# H723.net
KiCad netlist of a schematic drawn in EasyEDA Pro
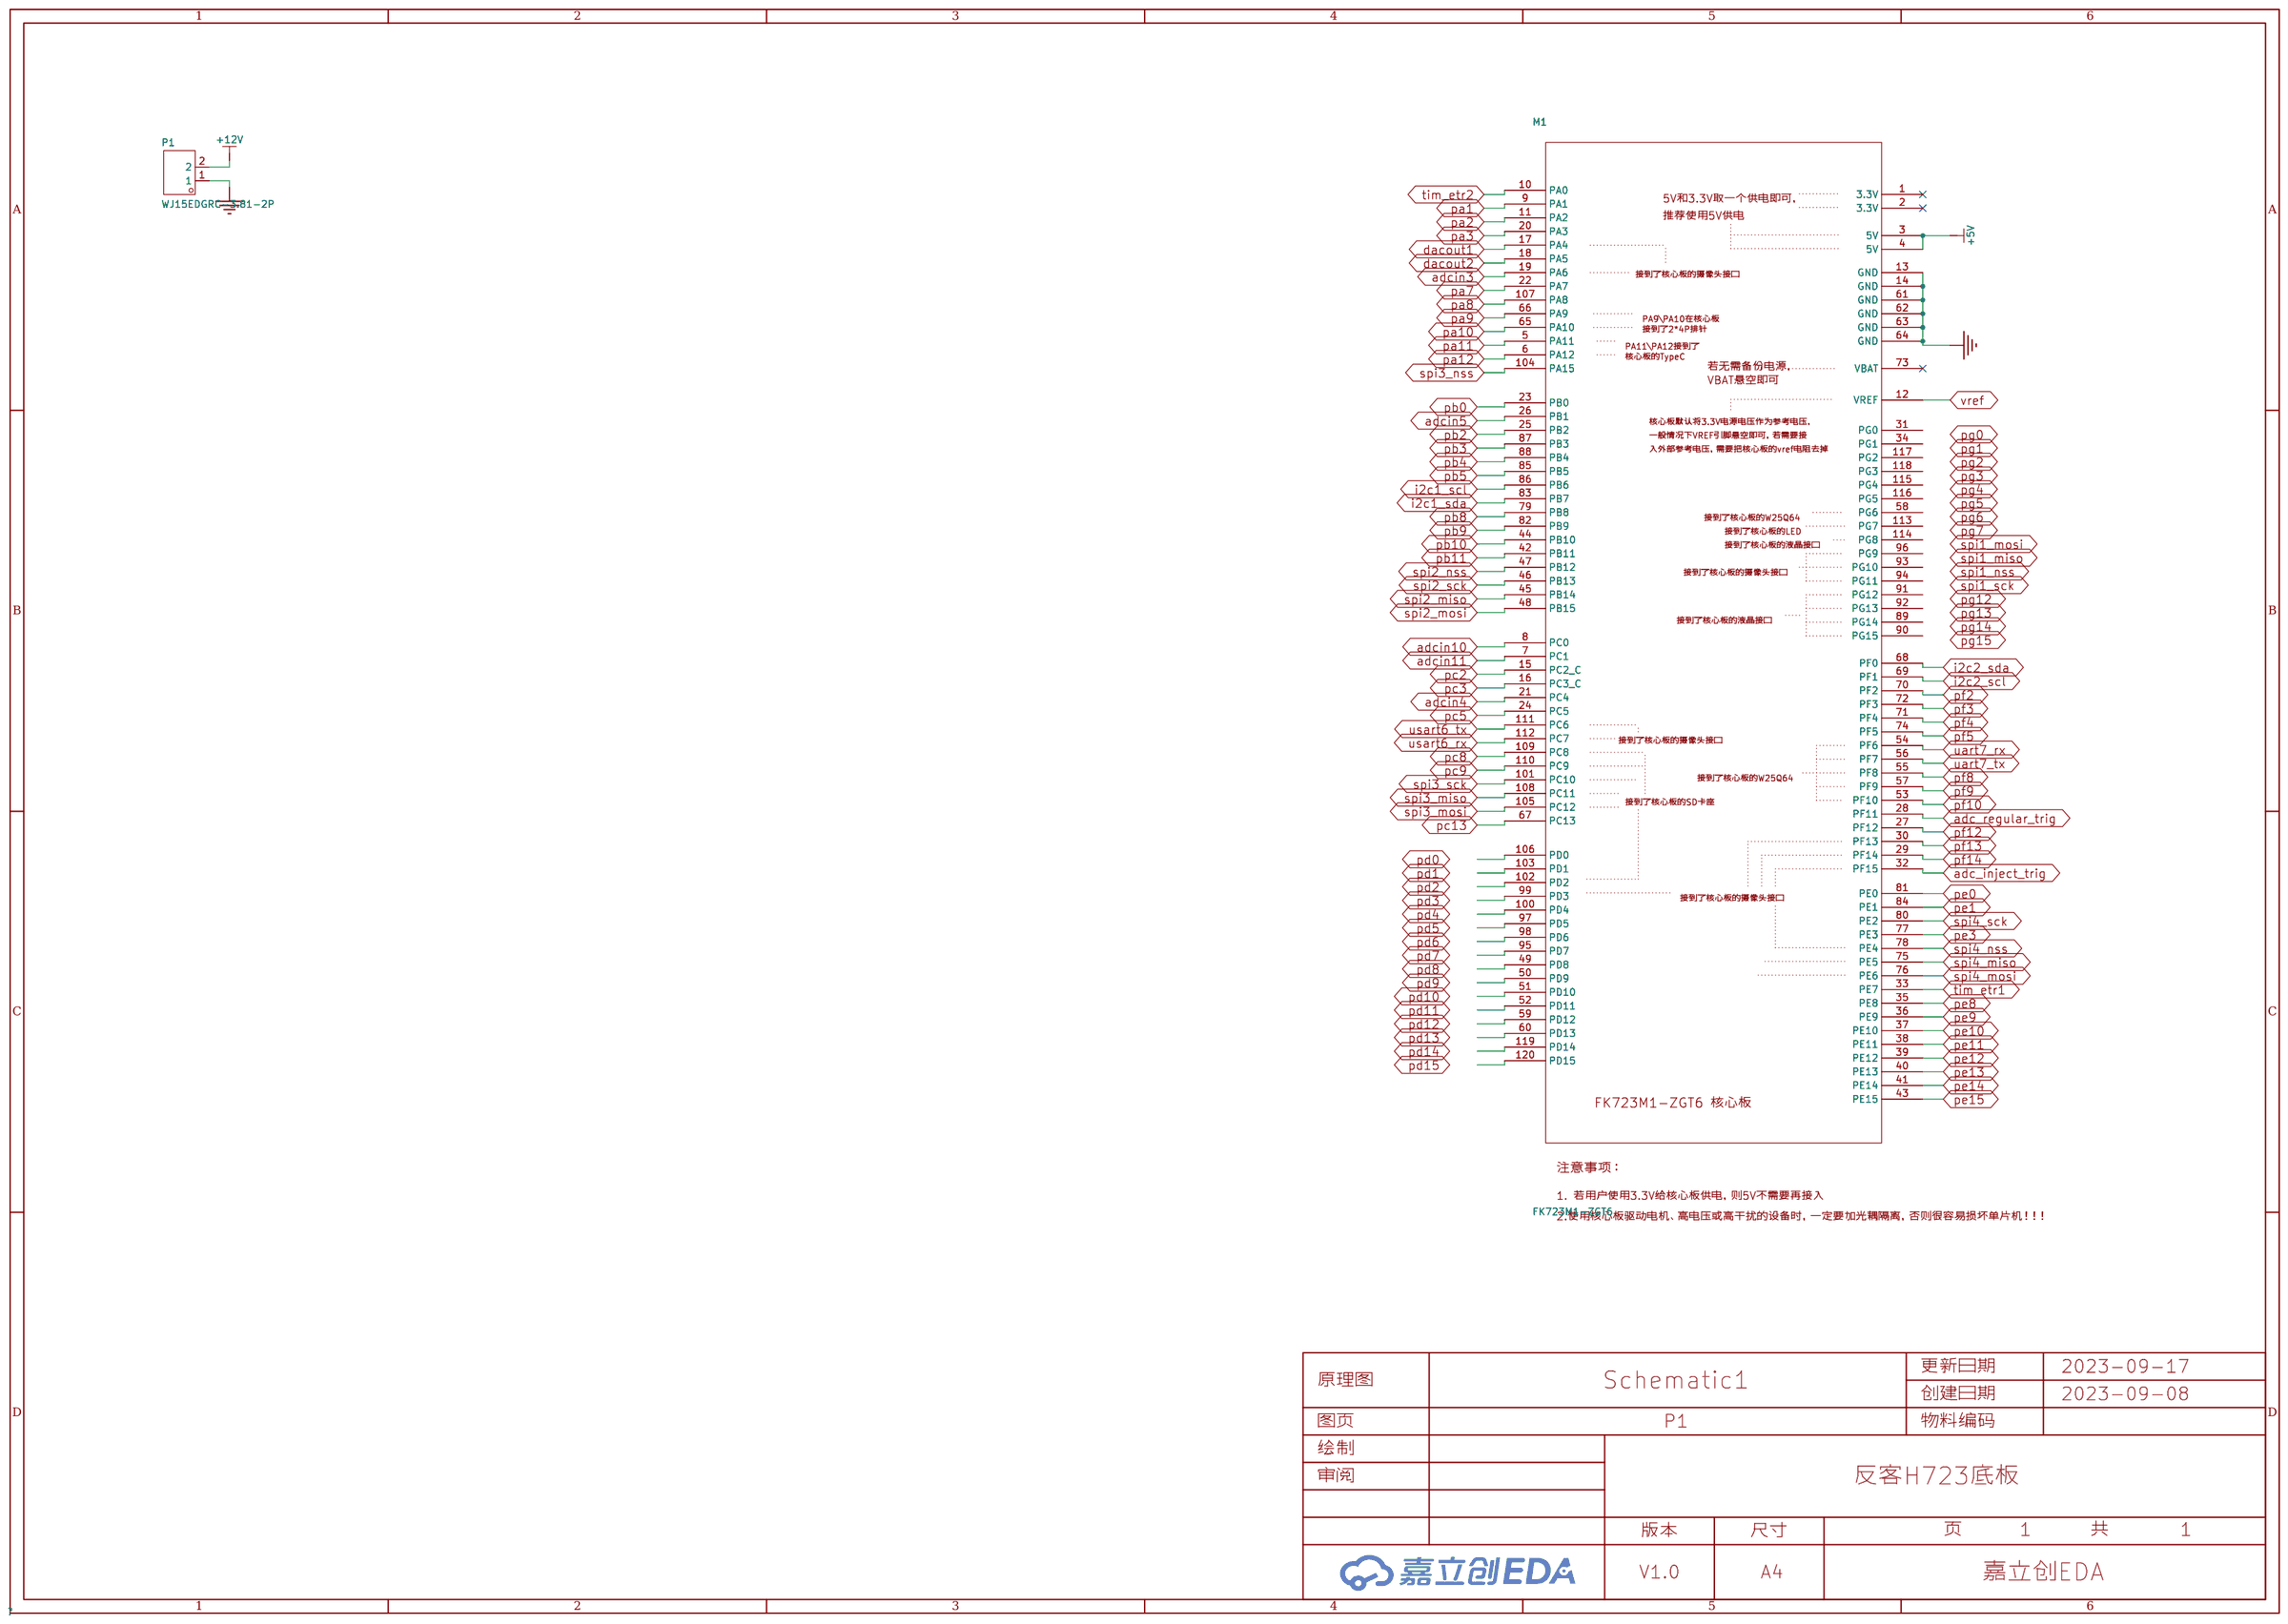
[diagram p0: schematic sheet]

(export (version "E")
  (design (tool "Eeschema 10.0.6"))
  (components
    (comp (ref "M1")
      (value "FK723M1-ZGT6")
      (footprint "easyedapro:FK723M1-ZGT6")
      (libsource (lib "easyedapro") (part "FK723M1-ZGT6"))
    )
    (comp (ref "P1")
      (value "WJ15EDGRC-3.81-2P")
      (footprint "easyedapro:CONN-TH_2P-P3.81_WJ15EDGRC-3.81-2P")
      (description "连接器类型:板端/插座-闭口;间距:3.81mm;排数:1;每排PIN数:2;安装方式:弯针;颜色:绿色;")
      (fields (field (name "Manufacturer") "KANGNEX(康奈克斯电气)"))
      (libsource (lib "easyedapro") (part "WJ15EDGRC-3.81-2P"))
    )
  )
  (nets
    (net (code "1") (name "+5V") (class "Default")
      (node (ref "M1") (pin "3") (pinfunction "5V_3") (pintype "input"))
      (node (ref "M1") (pin "4") (pinfunction "5V_4") (pintype "input"))
    )
    (net (code "2") (name "+12V") (class "Default")
      (node (ref "P1") (pin "2") (pinfunction "2_2") (pintype "input"))
    )
    (net (code "3") (name "GND") (class "Default")
      (node (ref "M1") (pin "13") (pinfunction "GND_13") (pintype "input"))
      (node (ref "M1") (pin "14") (pinfunction "GND_14") (pintype "input"))
      (node (ref "M1") (pin "61") (pinfunction "GND_61") (pintype "input"))
      (node (ref "M1") (pin "62") (pinfunction "GND_62") (pintype "input"))
      (node (ref "M1") (pin "63") (pinfunction "GND_63") (pintype "input"))
      (node (ref "M1") (pin "64") (pinfunction "GND_64") (pintype "input"))
      (node (ref "P1") (pin "1") (pinfunction "1_1") (pintype "input"))
    )
    (net (code "4") (name "adc_inject_trig") (class "Default")
      (node (ref "M1") (pin "32") (pinfunction "PF15_32") (pintype "input"))
    )
    (net (code "5") (name "adc_regular_trig") (class "Default")
      (node (ref "M1") (pin "28") (pinfunction "PF11_28") (pintype "input"))
    )
    (net (code "6") (name "adcin3") (class "Default")
      (node (ref "M1") (pin "19") (pinfunction "PA6_19") (pintype "input"))
    )
    (net (code "7") (name "adcin4") (class "Default")
      (node (ref "M1") (pin "21") (pinfunction "PC4_21") (pintype "input"))
    )
    (net (code "8") (name "adcin5") (class "Default")
      (node (ref "M1") (pin "26") (pinfunction "PB1_26") (pintype "input"))
    )
    (net (code "9") (name "adcin10") (class "Default")
      (node (ref "M1") (pin "8") (pinfunction "PC0_8") (pintype "input"))
    )
    (net (code "10") (name "adcin11") (class "Default")
      (node (ref "M1") (pin "7") (pinfunction "PC1_7") (pintype "input"))
    )
    (net (code "11") (name "dacout1") (class "Default")
      (node (ref "M1") (pin "17") (pinfunction "PA4_17") (pintype "input"))
    )
    (net (code "12") (name "dacout2") (class "Default")
      (node (ref "M1") (pin "18") (pinfunction "PA5_18") (pintype "input"))
    )
    (net (code "13") (name "i2c1_scl") (class "Default")
      (node (ref "M1") (pin "86") (pinfunction "PB6_86") (pintype "input"))
    )
    (net (code "14") (name "i2c1_sda") (class "Default")
      (node (ref "M1") (pin "83") (pinfunction "PB7_83") (pintype "input"))
    )
    (net (code "15") (name "i2c2_scl") (class "Default")
      (node (ref "M1") (pin "69") (pinfunction "PF1_69") (pintype "input"))
    )
    (net (code "16") (name "i2c2_sda") (class "Default")
      (node (ref "M1") (pin "68") (pinfunction "PF0_68") (pintype "input"))
    )
    (net (code "17") (name "pa1") (class "Default")
      (node (ref "M1") (pin "9") (pinfunction "PA1_9") (pintype "input"))
    )
    (net (code "18") (name "pa2") (class "Default")
      (node (ref "M1") (pin "11") (pinfunction "PA2_11") (pintype "input"))
    )
    (net (code "19") (name "pa3") (class "Default")
      (node (ref "M1") (pin "20") (pinfunction "PA3_20") (pintype "input"))
    )
    (net (code "20") (name "pa7") (class "Default")
      (node (ref "M1") (pin "22") (pinfunction "PA7_22") (pintype "input"))
    )
    (net (code "21") (name "pa8") (class "Default")
      (node (ref "M1") (pin "107") (pinfunction "PA8_107") (pintype "input"))
    )
    (net (code "22") (name "pa9") (class "Default")
      (node (ref "M1") (pin "66") (pinfunction "PA9_66") (pintype "input"))
    )
    (net (code "23") (name "pa10") (class "Default")
      (node (ref "M1") (pin "65") (pinfunction "PA10_65") (pintype "input"))
    )
    (net (code "24") (name "pa11") (class "Default")
      (node (ref "M1") (pin "5") (pinfunction "PA11_5") (pintype "input"))
    )
    (net (code "25") (name "pa12") (class "Default")
      (node (ref "M1") (pin "6") (pinfunction "PA12_6") (pintype "input"))
    )
    (net (code "26") (name "pb0") (class "Default")
      (node (ref "M1") (pin "23") (pinfunction "PB0_23") (pintype "input"))
    )
    (net (code "27") (name "pb2") (class "Default")
      (node (ref "M1") (pin "25") (pinfunction "PB2_25") (pintype "input"))
    )
    (net (code "28") (name "pb3") (class "Default")
      (node (ref "M1") (pin "87") (pinfunction "PB3_87") (pintype "input"))
    )
    (net (code "29") (name "pb4") (class "Default")
      (node (ref "M1") (pin "88") (pinfunction "PB4_88") (pintype "input"))
    )
    (net (code "30") (name "pb5") (class "Default")
      (node (ref "M1") (pin "85") (pinfunction "PB5_85") (pintype "input"))
    )
    (net (code "31") (name "pb8") (class "Default")
      (node (ref "M1") (pin "79") (pinfunction "PB8_79") (pintype "input"))
    )
    (net (code "32") (name "pb9") (class "Default")
      (node (ref "M1") (pin "82") (pinfunction "PB9_82") (pintype "input"))
    )
    (net (code "33") (name "pb10") (class "Default")
      (node (ref "M1") (pin "44") (pinfunction "PB10_44") (pintype "input"))
    )
    (net (code "34") (name "pb11") (class "Default")
      (node (ref "M1") (pin "42") (pinfunction "PB11_42") (pintype "input"))
    )
    (net (code "35") (name "pc2") (class "Default")
      (node (ref "M1") (pin "15") (pinfunction "PC2_C_15") (pintype "input"))
    )
    (net (code "36") (name "pc3") (class "Default")
      (node (ref "M1") (pin "16") (pinfunction "PC3_C_16") (pintype "input"))
    )
    (net (code "37") (name "pc5") (class "Default")
      (node (ref "M1") (pin "24") (pinfunction "PC5_24") (pintype "input"))
    )
    (net (code "38") (name "pc8") (class "Default")
      (node (ref "M1") (pin "109") (pinfunction "PC8_109") (pintype "input"))
    )
    (net (code "39") (name "pc9") (class "Default")
      (node (ref "M1") (pin "110") (pinfunction "PC9_110") (pintype "input"))
    )
    (net (code "40") (name "pc13") (class "Default")
      (node (ref "M1") (pin "67") (pinfunction "PC13_67") (pintype "input"))
    )
    (net (code "57") (name "pe0") (class "Default")
      (node (ref "M1") (pin "81") (pinfunction "PE0_81") (pintype "input"))
    )
    (net (code "58") (name "pe1") (class "Default")
      (node (ref "M1") (pin "84") (pinfunction "PE1_84") (pintype "input"))
    )
    (net (code "59") (name "pe3") (class "Default")
      (node (ref "M1") (pin "77") (pinfunction "PE3_77") (pintype "input"))
    )
    (net (code "60") (name "pe8") (class "Default")
      (node (ref "M1") (pin "35") (pinfunction "PE8_35") (pintype "input"))
    )
    (net (code "61") (name "pe9") (class "Default")
      (node (ref "M1") (pin "36") (pinfunction "PE9_36") (pintype "input"))
    )
    (net (code "62") (name "pe10") (class "Default")
      (node (ref "M1") (pin "37") (pinfunction "PE10_37") (pintype "input"))
    )
    (net (code "63") (name "pe11") (class "Default")
      (node (ref "M1") (pin "38") (pinfunction "PE11_38") (pintype "input"))
    )
    (net (code "64") (name "pe12") (class "Default")
      (node (ref "M1") (pin "39") (pinfunction "PE12_39") (pintype "input"))
    )
    (net (code "65") (name "pe13") (class "Default")
      (node (ref "M1") (pin "40") (pinfunction "PE13_40") (pintype "input"))
    )
    (net (code "66") (name "pe14") (class "Default")
      (node (ref "M1") (pin "41") (pinfunction "PE14_41") (pintype "input"))
    )
    (net (code "67") (name "pe15") (class "Default")
      (node (ref "M1") (pin "43") (pinfunction "PE15_43") (pintype "input"))
    )
    (net (code "68") (name "pf2") (class "Default")
      (node (ref "M1") (pin "70") (pinfunction "PF2_70") (pintype "input"))
    )
    (net (code "69") (name "pf3") (class "Default")
      (node (ref "M1") (pin "72") (pinfunction "PF3_72") (pintype "input"))
    )
    (net (code "70") (name "pf4") (class "Default")
      (node (ref "M1") (pin "71") (pinfunction "PF4_71") (pintype "input"))
    )
    (net (code "71") (name "pf5") (class "Default")
      (node (ref "M1") (pin "74") (pinfunction "PF5_74") (pintype "input"))
    )
    (net (code "72") (name "pf8") (class "Default")
      (node (ref "M1") (pin "55") (pinfunction "PF8_55") (pintype "input"))
    )
    (net (code "73") (name "pf9") (class "Default")
      (node (ref "M1") (pin "57") (pinfunction "PF9_57") (pintype "input"))
    )
    (net (code "74") (name "pf10") (class "Default")
      (node (ref "M1") (pin "53") (pinfunction "PF10_53") (pintype "input"))
    )
    (net (code "75") (name "pf12") (class "Default")
      (node (ref "M1") (pin "27") (pinfunction "PF12_27") (pintype "input"))
    )
    (net (code "76") (name "pf13") (class "Default")
      (node (ref "M1") (pin "30") (pinfunction "PF13_30") (pintype "input"))
    )
    (net (code "77") (name "pf14") (class "Default")
      (node (ref "M1") (pin "29") (pinfunction "PF14_29") (pintype "input"))
    )
    (net (code "94") (name "spi2_miso") (class "Default")
      (node (ref "M1") (pin "45") (pinfunction "PB14_45") (pintype "input"))
    )
    (net (code "95") (name "spi2_mosi") (class "Default")
      (node (ref "M1") (pin "48") (pinfunction "PB15_48") (pintype "input"))
    )
    (net (code "96") (name "spi2_nss") (class "Default")
      (node (ref "M1") (pin "47") (pinfunction "PB12_47") (pintype "input"))
    )
    (net (code "97") (name "spi2_sck") (class "Default")
      (node (ref "M1") (pin "46") (pinfunction "PB13_46") (pintype "input"))
    )
    (net (code "98") (name "spi3_miso") (class "Default")
      (node (ref "M1") (pin "108") (pinfunction "PC11_108") (pintype "input"))
    )
    (net (code "99") (name "spi3_mosi") (class "Default")
      (node (ref "M1") (pin "105") (pinfunction "PC12_105") (pintype "input"))
    )
    (net (code "100") (name "spi3_nss") (class "Default")
      (node (ref "M1") (pin "104") (pinfunction "PA15_104") (pintype "input"))
    )
    (net (code "101") (name "spi3_sck") (class "Default")
      (node (ref "M1") (pin "101") (pinfunction "PC10_101") (pintype "input"))
    )
    (net (code "102") (name "spi4_miso") (class "Default")
      (node (ref "M1") (pin "75") (pinfunction "PE5_75") (pintype "input"))
    )
    (net (code "103") (name "spi4_mosi") (class "Default")
      (node (ref "M1") (pin "76") (pinfunction "PE6_76") (pintype "input"))
    )
    (net (code "104") (name "spi4_nss") (class "Default")
      (node (ref "M1") (pin "78") (pinfunction "PE4_78") (pintype "input"))
    )
    (net (code "105") (name "spi4_sck") (class "Default")
      (node (ref "M1") (pin "80") (pinfunction "PE2_80") (pintype "input"))
    )
    (net (code "106") (name "tim_etr1") (class "Default")
      (node (ref "M1") (pin "33") (pinfunction "PE7_33") (pintype "input"))
    )
    (net (code "107") (name "tim_etr2") (class "Default")
      (node (ref "M1") (pin "10") (pinfunction "PA0_10") (pintype "input"))
    )
    (net (code "108") (name "uart7_rx") (class "Default")
      (node (ref "M1") (pin "54") (pinfunction "PF6_54") (pintype "input"))
    )
    (net (code "109") (name "uart7_tx") (class "Default")
      (node (ref "M1") (pin "56") (pinfunction "PF7_56") (pintype "input"))
    )
    (net (code "110") (name "unconnected-(M1-3.3V-Pad1)") (class "Default")
      (node (ref "M1") (pin "1") (pinfunction "3.3V_1") (pintype "input+no_connect"))
    )
    (net (code "111") (name "unconnected-(M1-3.3V-Pad2)") (class "Default")
      (node (ref "M1") (pin "2") (pinfunction "3.3V_2") (pintype "input+no_connect"))
    )
    (net (code "112") (name "unconnected-(M1-PD0-Pad106)") (class "Default")
      (node (ref "M1") (pin "106") (pinfunction "PD0_106") (pintype "input"))
    )
    (net (code "113") (name "unconnected-(M1-PD1-Pad103)") (class "Default")
      (node (ref "M1") (pin "103") (pinfunction "PD1_103") (pintype "input"))
    )
    (net (code "114") (name "unconnected-(M1-PD2-Pad102)") (class "Default")
      (node (ref "M1") (pin "102") (pinfunction "PD2_102") (pintype "input"))
    )
    (net (code "115") (name "unconnected-(M1-PD3-Pad99)") (class "Default")
      (node (ref "M1") (pin "99") (pinfunction "PD3_99") (pintype "input"))
    )
    (net (code "116") (name "unconnected-(M1-PD4-Pad100)") (class "Default")
      (node (ref "M1") (pin "100") (pinfunction "PD4_100") (pintype "input"))
    )
    (net (code "117") (name "unconnected-(M1-PD5-Pad97)") (class "Default")
      (node (ref "M1") (pin "97") (pinfunction "PD5_97") (pintype "input"))
    )
    (net (code "118") (name "unconnected-(M1-PD6-Pad98)") (class "Default")
      (node (ref "M1") (pin "98") (pinfunction "PD6_98") (pintype "input"))
    )
    (net (code "119") (name "unconnected-(M1-PD7-Pad95)") (class "Default")
      (node (ref "M1") (pin "95") (pinfunction "PD7_95") (pintype "input"))
    )
    (net (code "120") (name "unconnected-(M1-PD8-Pad49)") (class "Default")
      (node (ref "M1") (pin "49") (pinfunction "PD8_49") (pintype "input"))
    )
    (net (code "121") (name "unconnected-(M1-PD9-Pad50)") (class "Default")
      (node (ref "M1") (pin "50") (pinfunction "PD9_50") (pintype "input"))
    )
    (net (code "122") (name "unconnected-(M1-PD10-Pad51)") (class "Default")
      (node (ref "M1") (pin "51") (pinfunction "PD10_51") (pintype "input"))
    )
    (net (code "123") (name "unconnected-(M1-PD11-Pad52)") (class "Default")
      (node (ref "M1") (pin "52") (pinfunction "PD11_52") (pintype "input"))
    )
    (net (code "124") (name "unconnected-(M1-PD12-Pad59)") (class "Default")
      (node (ref "M1") (pin "59") (pinfunction "PD12_59") (pintype "input"))
    )
    (net (code "125") (name "unconnected-(M1-PD13-Pad60)") (class "Default")
      (node (ref "M1") (pin "60") (pinfunction "PD13_60") (pintype "input"))
    )
    (net (code "126") (name "unconnected-(M1-PD14-Pad119)") (class "Default")
      (node (ref "M1") (pin "119") (pinfunction "PD14_119") (pintype "input"))
    )
    (net (code "127") (name "unconnected-(M1-PD15-Pad120)") (class "Default")
      (node (ref "M1") (pin "120") (pinfunction "PD15_120") (pintype "input"))
    )
    (net (code "128") (name "unconnected-(M1-PG0-Pad31)") (class "Default")
      (node (ref "M1") (pin "31") (pinfunction "PG0_31") (pintype "input"))
    )
    (net (code "129") (name "unconnected-(M1-PG1-Pad34)") (class "Default")
      (node (ref "M1") (pin "34") (pinfunction "PG1_34") (pintype "input"))
    )
    (net (code "130") (name "unconnected-(M1-PG2-Pad117)") (class "Default")
      (node (ref "M1") (pin "117") (pinfunction "PG2_117") (pintype "input"))
    )
    (net (code "131") (name "unconnected-(M1-PG3-Pad118)") (class "Default")
      (node (ref "M1") (pin "118") (pinfunction "PG3_118") (pintype "input"))
    )
    (net (code "132") (name "unconnected-(M1-PG4-Pad115)") (class "Default")
      (node (ref "M1") (pin "115") (pinfunction "PG4_115") (pintype "input"))
    )
    (net (code "133") (name "unconnected-(M1-PG5-Pad116)") (class "Default")
      (node (ref "M1") (pin "116") (pinfunction "PG5_116") (pintype "input"))
    )
    (net (code "134") (name "unconnected-(M1-PG6-Pad58)") (class "Default")
      (node (ref "M1") (pin "58") (pinfunction "PG6_58") (pintype "input"))
    )
    (net (code "135") (name "unconnected-(M1-PG7-Pad113)") (class "Default")
      (node (ref "M1") (pin "113") (pinfunction "PG7_113") (pintype "input"))
    )
    (net (code "136") (name "unconnected-(M1-PG8-Pad114)") (class "Default")
      (node (ref "M1") (pin "114") (pinfunction "PG8_114") (pintype "input"))
    )
    (net (code "137") (name "unconnected-(M1-PG9-Pad96)") (class "Default")
      (node (ref "M1") (pin "96") (pinfunction "PG9_96") (pintype "input"))
    )
    (net (code "138") (name "unconnected-(M1-PG10-Pad93)") (class "Default")
      (node (ref "M1") (pin "93") (pinfunction "PG10_93") (pintype "input"))
    )
    (net (code "139") (name "unconnected-(M1-PG11-Pad94)") (class "Default")
      (node (ref "M1") (pin "94") (pinfunction "PG11_94") (pintype "input"))
    )
    (net (code "140") (name "unconnected-(M1-PG12-Pad91)") (class "Default")
      (node (ref "M1") (pin "91") (pinfunction "PG12_91") (pintype "input"))
    )
    (net (code "141") (name "unconnected-(M1-PG13-Pad92)") (class "Default")
      (node (ref "M1") (pin "92") (pinfunction "PG13_92") (pintype "input"))
    )
    (net (code "142") (name "unconnected-(M1-PG14-Pad89)") (class "Default")
      (node (ref "M1") (pin "89") (pinfunction "PG14_89") (pintype "input"))
    )
    (net (code "143") (name "unconnected-(M1-PG15-Pad90)") (class "Default")
      (node (ref "M1") (pin "90") (pinfunction "PG15_90") (pintype "input"))
    )
    (net (code "144") (name "unconnected-(M1-VBAT-Pad73)") (class "Default")
      (node (ref "M1") (pin "73") (pinfunction "VBAT_73") (pintype "input+no_connect"))
    )
    (net (code "145") (name "usart6_rx") (class "Default")
      (node (ref "M1") (pin "112") (pinfunction "PC7_112") (pintype "input"))
    )
    (net (code "146") (name "usart6_tx") (class "Default")
      (node (ref "M1") (pin "111") (pinfunction "PC6_111") (pintype "input"))
    )
    (net (code "147") (name "vref") (class "Default")
      (node (ref "M1") (pin "12") (pinfunction "VREF_12") (pintype "input"))
    )
  )
)
